# ISOinputs.net
KiCad netlist of a schematic drawn in Altium Designer
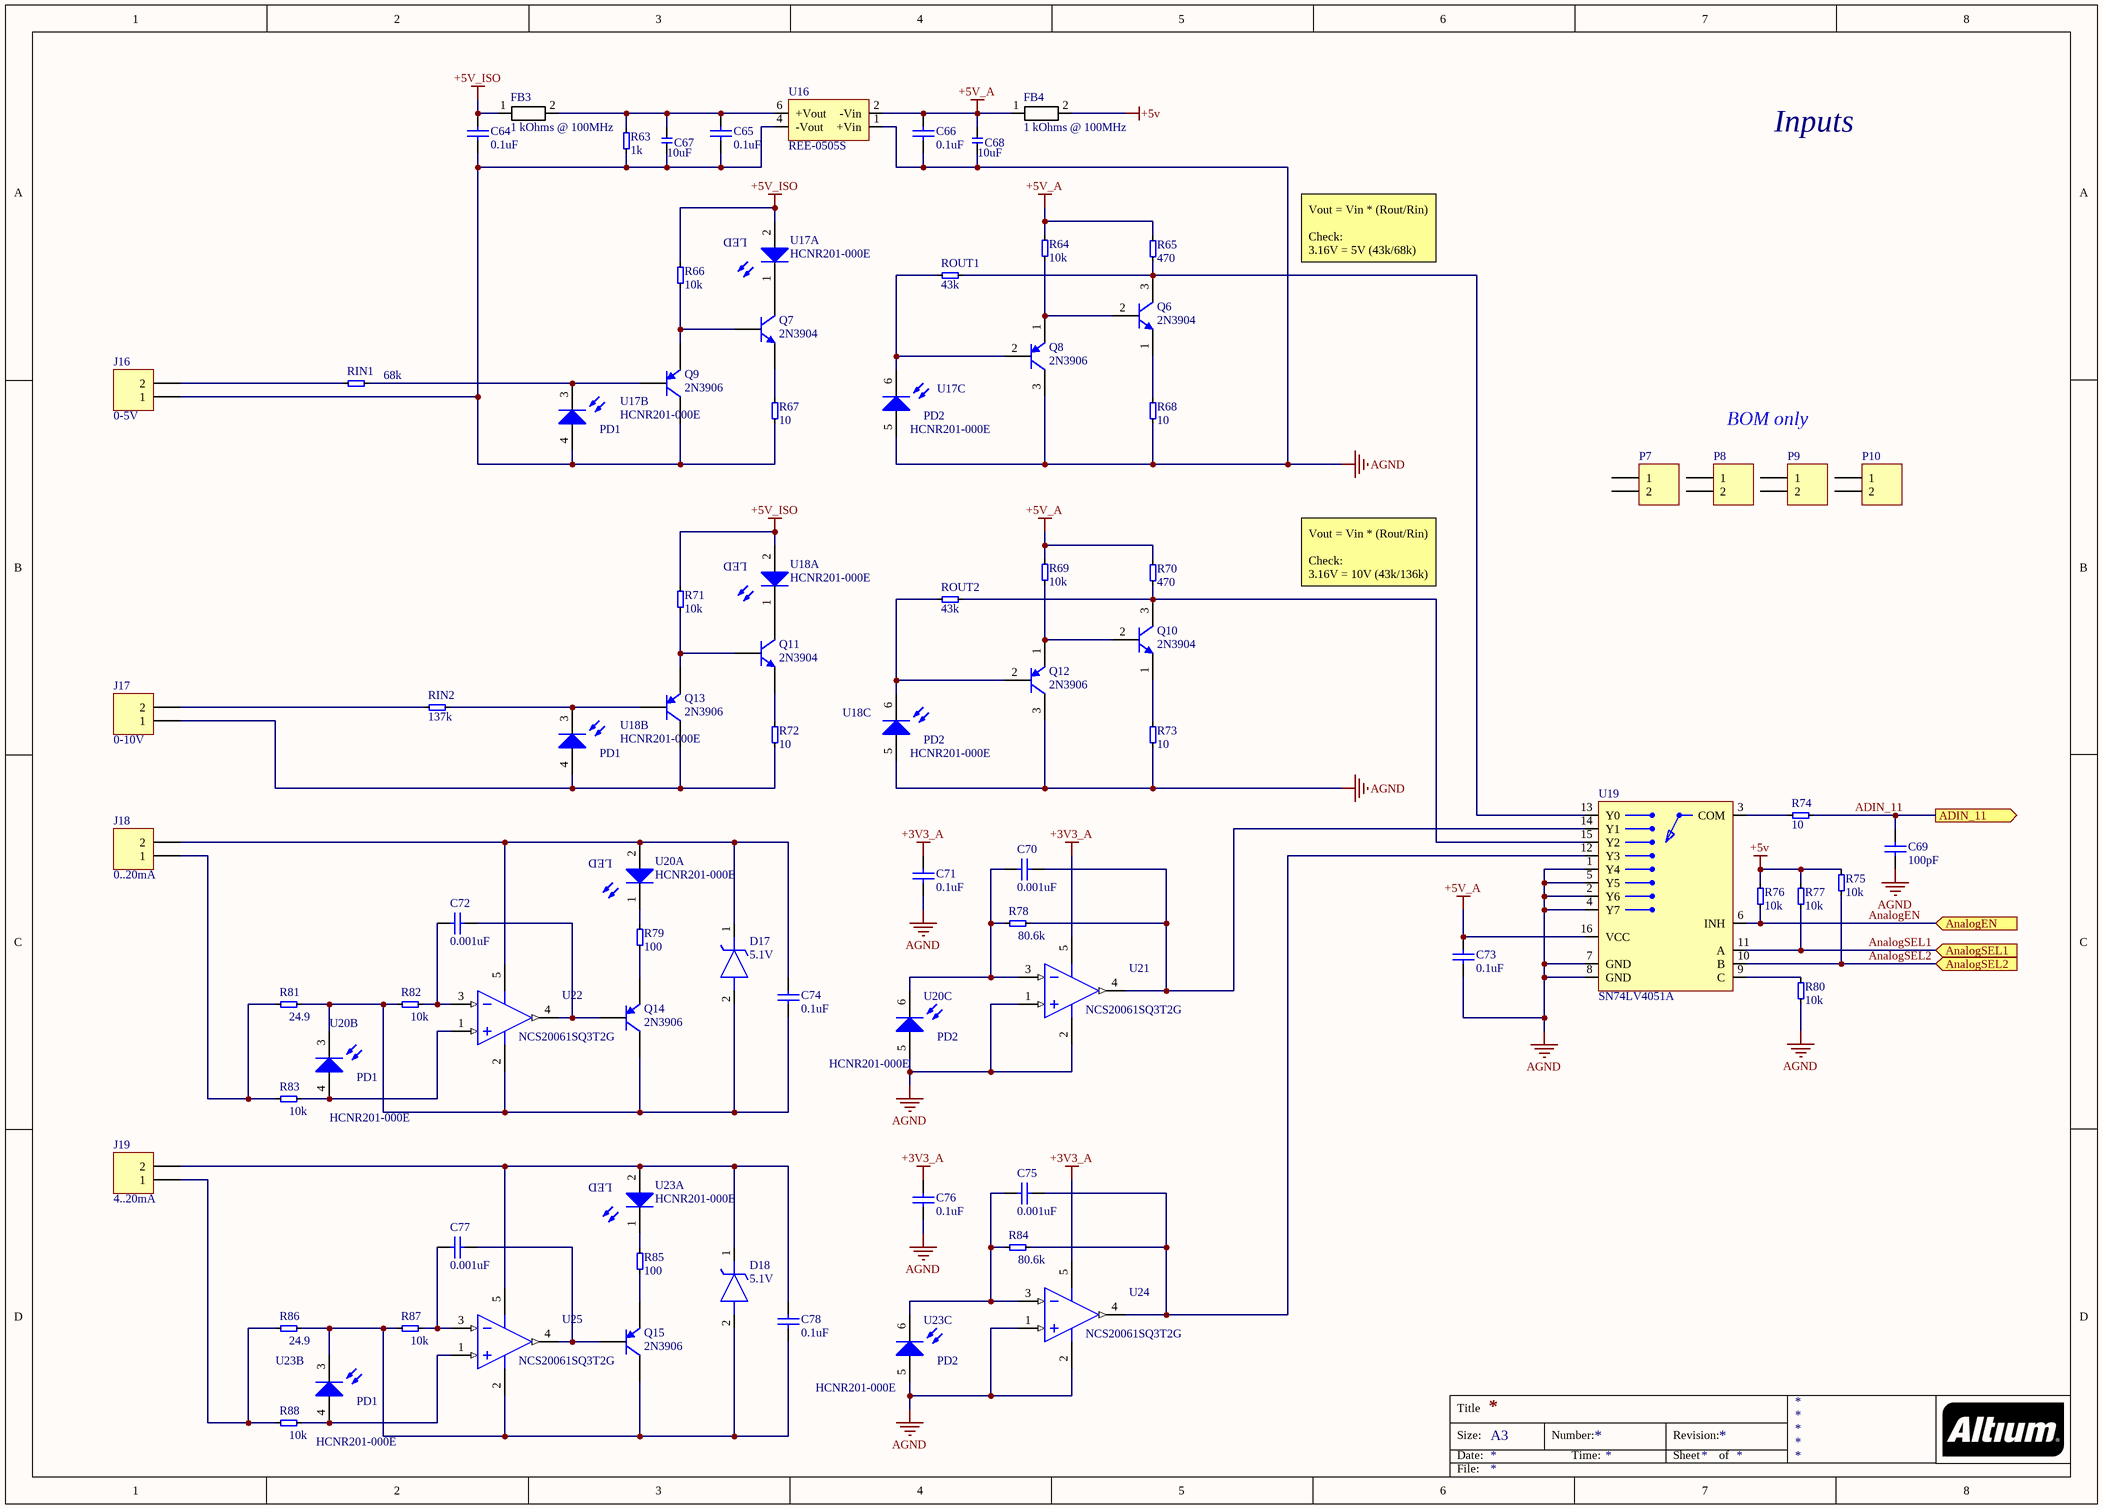
[diagram p0: ISOinputs.SchDoc]

(export (version "E")
  (design (tool "Eeschema 10.0.6"))
  (components
    (comp (ref "C64")
      (value "0.1uF")
      (footprint "C_ceramic_0603")
      (description "CAP CER 0.1UF 50V X7R 0603")
      (fields
        (field (name "MANUFACTURER") "Yageo")
        (field (name "MANUFACTURER PART NUMBER") "CC0603KPX7R9BB104")
      )
      (libsource (lib "Miscellaneous Devices") (part "Cap"))
    )
    (comp (ref "C65")
      (value "0.1uF")
      (footprint "C_ceramic_0603")
      (description "CAP CER 0.1UF 50V X7R 0603")
      (fields
        (field (name "MANUFACTURER") "Yageo")
        (field (name "MANUFACTURER PART NUMBER") "CC0603KPX7R9BB104")
      )
      (libsource (lib "Miscellaneous Devices") (part "Cap"))
    )
    (comp (ref "C66")
      (value "0.1uF")
      (footprint "C_ceramic_0603")
      (description "CAP CER 0.1UF 50V X7R 0603")
      (fields
        (field (name "MANUFACTURER") "Yageo")
        (field (name "MANUFACTURER PART NUMBER") "CC0603KPX7R9BB104")
      )
      (libsource (lib "Miscellaneous Devices") (part "Cap"))
    )
    (comp (ref "C67")
      (value "10uF")
      (footprint "C0603")
      (description "CAP CER 10UF 10V X5R 0603")
      (fields
        (field (name "MANUFACTURER") "Murata")
        (field (name "MANUFACTURER PART NUMBER") "GRM188R61A106KE69D")
      )
      (libsource (lib "LED_LIB") (part "CAP_0603"))
    )
    (comp (ref "C68")
      (value "10uF")
      (footprint "C0603")
      (description "CAP CER 10UF 10V X5R 0603")
      (fields
        (field (name "MANUFACTURER") "Murata")
        (field (name "MANUFACTURER PART NUMBER") "GRM188R61A106KE69D")
      )
      (libsource (lib "LED_LIB") (part "CAP_0603"))
    )
    (comp (ref "C69")
      (value "100pF")
      (footprint "C_ceramic_0603")
      (description "CAP CER 100PF 50V C0G/NPO 0603")
      (fields
        (field (name "MANUFACTURER") "Yageo")
        (field (name "MANUFACTURER PART NUMBER") "CC0603JRNPO9BN101")
      )
      (libsource (lib "Miscellaneous Devices") (part "Cap"))
    )
    (comp (ref "C70")
      (value "0.001uF")
      (footprint "C_ceramic_0603")
      (description "CAP CER 1000PF 50V C0G/NPO 0603")
      (fields
        (field (name "MANUFACTURER") "Yageo")
        (field (name "MANUFACTURER PART NUMBER") "CC0603JRNPO9BN102")
      )
      (libsource (lib "Miscellaneous Devices") (part "Cap"))
    )
    (comp (ref "C71")
      (value "0.1uF")
      (footprint "C_ceramic_0603")
      (description "CAP CER 0.1UF 50V X7R 0603")
      (fields
        (field (name "MANUFACTURER") "Yageo")
        (field (name "MANUFACTURER PART NUMBER") "CC0603KPX7R9BB104")
      )
      (libsource (lib "Miscellaneous Devices") (part "Cap"))
    )
    (comp (ref "C72")
      (value "0.001uF")
      (footprint "C_ceramic_0603")
      (description "CAP CER 1000PF 50V C0G/NPO 0603")
      (fields
        (field (name "MANUFACTURER") "Yageo")
        (field (name "MANUFACTURER PART NUMBER") "CC0603JRNPO9BN102")
      )
      (libsource (lib "Miscellaneous Devices") (part "Cap"))
    )
    (comp (ref "C73")
      (value "0.1uF")
      (footprint "C_ceramic_0603")
      (description "CAP CER 0.1UF 50V X7R 0603")
      (fields
        (field (name "MANUFACTURER") "Yageo")
        (field (name "MANUFACTURER PART NUMBER") "CC0603KPX7R9BB104")
      )
      (libsource (lib "Miscellaneous Devices") (part "Cap"))
    )
    (comp (ref "C74")
      (value "0.1uF")
      (footprint "C_ceramic_0603")
      (description "CAP CER 0.1UF 50V X7R 0603")
      (fields
        (field (name "MANUFACTURER") "Yageo")
        (field (name "MANUFACTURER PART NUMBER") "CC0603KPX7R9BB104")
      )
      (libsource (lib "Miscellaneous Devices") (part "Cap"))
    )
    (comp (ref "C75")
      (value "0.001uF")
      (footprint "C_ceramic_0603")
      (description "CAP CER 1000PF 50V C0G/NPO 0603")
      (fields
        (field (name "MANUFACTURER") "Yageo")
        (field (name "MANUFACTURER PART NUMBER") "CC0603JRNPO9BN102")
      )
      (libsource (lib "Miscellaneous Devices") (part "Cap"))
    )
    (comp (ref "C76")
      (value "0.1uF")
      (footprint "C_ceramic_0603")
      (description "CAP CER 0.1UF 50V X7R 0603")
      (fields
        (field (name "MANUFACTURER") "Yageo")
        (field (name "MANUFACTURER PART NUMBER") "CC0603KPX7R9BB104")
      )
      (libsource (lib "Miscellaneous Devices") (part "Cap"))
    )
    (comp (ref "C77")
      (value "0.001uF")
      (footprint "C_ceramic_0603")
      (description "CAP CER 1000PF 50V C0G/NPO 0603")
      (fields
        (field (name "MANUFACTURER") "Yageo")
        (field (name "MANUFACTURER PART NUMBER") "CC0603JRNPO9BN102")
      )
      (libsource (lib "Miscellaneous Devices") (part "Cap"))
    )
    (comp (ref "C78")
      (value "0.1uF")
      (footprint "C_ceramic_0603")
      (description "CAP CER 0.1UF 50V X7R 0603")
      (fields
        (field (name "MANUFACTURER") "Yageo")
        (field (name "MANUFACTURER PART NUMBER") "CC0603KPX7R9BB104")
      )
      (libsource (lib "Miscellaneous Devices") (part "Cap"))
    )
    (comp (ref "D17")
      (value "5.1V")
      (footprint "SOD_123_CA")
      (description "DIODE ZENER 5.1V 365MW SOD123")
      (fields (field (name "MANUFACTURER") "Nexperia") (field (name "MANUFACTURER PART NUMBER") "PDZ5.1BGWJ"))
      (libsource (lib "MY SCH LIB") (part "ZNR_PLZ5V1C-HG3_H"))
    )
    (comp (ref "D18")
      (value "5.1V")
      (footprint "SOD_123_CA")
      (description "DIODE ZENER 5.1V 365MW SOD123")
      (fields (field (name "MANUFACTURER") "Nexperia") (field (name "MANUFACTURER PART NUMBER") "PDZ5.1BGWJ"))
      (libsource (lib "MY SCH LIB") (part "ZNR_PLZ5V1C-HG3_H"))
    )
    (comp (ref "FB3")
      (value "1 kOhms @ 100MHz")
      (footprint "FB 16080")
      (description "FERRITE BEAD 1 KOHM 0603 1LN")
      (fields
        (field (name "MANUFACTURER") "Wurth Electronics")
        (field (name "MANUFACTURER PART NUMBER") "74279266")
      )
      (libsource (lib "MY SCH LIB") (part "Ferrite bead"))
    )
    (comp (ref "FB4")
      (value "1 kOhms @ 100MHz")
      (footprint "FB 16080")
      (description "FERRITE BEAD 1 KOHM 0603 1LN")
      (fields
        (field (name "MANUFACTURER") "Wurth Electronics")
        (field (name "MANUFACTURER PART NUMBER") "74279266")
      )
      (libsource (lib "MY SCH LIB") (part "Ferrite bead"))
    )
    (comp (ref "J16")
      (value "CIM025P5")
      (footprint "CON2_P5.08_CIM025P5")
      (description "TERM BLK 2P SIDE ENT 5.08MM PCB")
      (fields (field (name "MANUFACTURER") "Sauro"))
      (libsource (lib "") (part "Header 2_1"))
    )
    (comp (ref "J17")
      (value "CIM025P5")
      (footprint "CON2_P5.08_CIM025P5")
      (description "TERM BLK 2P SIDE ENT 5.08MM PCB")
      (fields (field (name "MANUFACTURER") "Sauro"))
      (libsource (lib "") (part "Header 2_1"))
    )
    (comp (ref "J18")
      (value "CIM025P5")
      (footprint "CON2_P5.08_CIM025P5")
      (description "TERM BLK 2P SIDE ENT 5.08MM PCB")
      (fields (field (name "MANUFACTURER") "Sauro"))
      (libsource (lib "") (part "Header 2_1"))
    )
    (comp (ref "J19")
      (value "CIM025P5")
      (footprint "CON2_P5.08_CIM025P5")
      (description "TERM BLK 2P SIDE ENT 5.08MM PCB")
      (fields (field (name "MANUFACTURER") "Sauro"))
      (libsource (lib "") (part "Header 2_1"))
    )
    (comp (ref "P7")
      (value "BOM ONLY")
      (description "Plug")
      (fields (field (name "MANUFACTURER") "Sauro") (field (name "MANUFACTURER PART NUMBER") "CIF02005"))
      (libsource (lib "Miscellaneous Connectors") (part "Header 2"))
    )
    (comp (ref "P8")
      (value "BOM ONLY")
      (description "Plug")
      (fields (field (name "MANUFACTURER") "Sauro") (field (name "MANUFACTURER PART NUMBER") "CIF02005"))
      (libsource (lib "Miscellaneous Connectors") (part "Header 2"))
    )
    (comp (ref "P9")
      (value "BOM ONLY")
      (description "Plug")
      (fields (field (name "MANUFACTURER") "Sauro") (field (name "MANUFACTURER PART NUMBER") "CIF02005"))
      (libsource (lib "Miscellaneous Connectors") (part "Header 2"))
    )
    (comp (ref "P10")
      (value "BOM ONLY")
      (description "Plug")
      (fields (field (name "MANUFACTURER") "Sauro") (field (name "MANUFACTURER PART NUMBER") "CIF02005"))
      (libsource (lib "Miscellaneous Connectors") (part "Header 2"))
    )
    (comp (ref "Q6")
      (value "2N3904")
      (footprint "TO-92A")
      (description "TRANS NPN 40V 0.2A TO-92")
      (fields
        (field (name "MANUFACTURER") "ON Semiconductor / Fairchild")
        (field (name "MANUFACTURER PART NUMBER") "2N3904BU")
      )
      (libsource (lib "") (part "2N3904_1"))
    )
    (comp (ref "Q7")
      (value "2N3904")
      (footprint "TO-92A")
      (description "TRANS NPN 40V 0.2A TO-92")
      (fields
        (field (name "MANUFACTURER") "ON Semiconductor / Fairchild")
        (field (name "MANUFACTURER PART NUMBER") "2N3904BU")
      )
      (libsource (lib "Miscellaneous Devices") (part "2N3904"))
    )
    (comp (ref "Q8")
      (value "2N3906")
      (footprint "TO-92A")
      (description "TRANS PNP 40V TO-92")
      (fields
        (field (name "MANUFACTURER") "Central Semiconductor")
        (field (name "PUBLISHER") "Altium Limited")
      )
      (libsource (lib "Miscellaneous Devices") (part "2N3906"))
    )
    (comp (ref "Q9")
      (value "2N3906")
      (footprint "TO-92A")
      (description "TRANS PNP 40V TO-92")
      (fields
        (field (name "MANUFACTURER") "Central Semiconductor")
        (field (name "PUBLISHER") "Altium Limited")
      )
      (libsource (lib "") (part "2N3906_1"))
    )
    (comp (ref "Q10")
      (value "2N3904")
      (footprint "TO-92A")
      (description "TRANS NPN 40V 0.2A TO-92")
      (fields
        (field (name "MANUFACTURER") "ON Semiconductor / Fairchild")
        (field (name "MANUFACTURER PART NUMBER") "2N3904BU")
      )
      (libsource (lib "") (part "2N3904_1"))
    )
    (comp (ref "Q11")
      (value "2N3904")
      (footprint "TO-92A")
      (description "TRANS NPN 40V 0.2A TO-92")
      (fields
        (field (name "MANUFACTURER") "ON Semiconductor / Fairchild")
        (field (name "MANUFACTURER PART NUMBER") "2N3904BU")
      )
      (libsource (lib "Miscellaneous Devices") (part "2N3904"))
    )
    (comp (ref "Q12")
      (value "2N3906")
      (footprint "TO-92A")
      (description "TRANS PNP 40V TO-92")
      (fields
        (field (name "MANUFACTURER") "Central Semiconductor")
        (field (name "PUBLISHER") "Altium Limited")
      )
      (libsource (lib "Miscellaneous Devices") (part "2N3906"))
    )
    (comp (ref "Q13")
      (value "2N3906")
      (footprint "TO-92A")
      (description "TRANS PNP 40V TO-92")
      (fields
        (field (name "MANUFACTURER") "Central Semiconductor")
        (field (name "PUBLISHER") "Altium Limited")
      )
      (libsource (lib "") (part "2N3906_1"))
    )
    (comp (ref "Q14")
      (value "2N3906")
      (footprint "TO-92A")
      (description "TRANS PNP 40V TO-92")
      (fields (field (name "MANUFACTURER") "Central Semiconductor"))
      (libsource (lib "") (part "2N3906_1"))
    )
    (comp (ref "Q15")
      (value "2N3906")
      (footprint "TO-92A")
      (description "TRANS PNP 40V TO-92")
      (fields (field (name "MANUFACTURER") "Central Semiconductor"))
      (libsource (lib "") (part "2N3906_1"))
    )
    (comp (ref "R63")
      (value "1k")
      (footprint "R_0603")
      (description "RES SMD 1K OHM 1% 1/10W 0603")
      (fields
        (field (name "MANUFACTURER") "Yageo")
        (field (name "MANUFACTURER PART NUMBER") "RC0603FR-071KL")
      )
      (libsource (lib "LED_LIB") (part "R_0402"))
    )
    (comp (ref "R64")
      (value "10k")
      (footprint "R_0603")
      (description "RES SMD 10K OHM 1% 1/10W 0603")
      (fields
        (field (name "MANUFACTURER") "Yageo")
        (field (name "MANUFACTURER PART NUMBER") "RC0603FR-0710KL")
      )
      (libsource (lib "LED_LIB") (part "R_0402"))
    )
    (comp (ref "R65")
      (value "470")
      (footprint "RES_C1206(3216)_M")
      (description "CRGP 1206 470R 1%")
      (fields (field (name "MANUFACTURER") "Yageo") (field (name "MANUFACTURER PART NUMBER") "CRGP1206F470R"))
      (libsource (lib "LED_LIB") (part "R_0402"))
    )
    (comp (ref "R66")
      (value "10k")
      (footprint "R_0603")
      (description "RES SMD 10K OHM 1% 1/10W 0603")
      (fields
        (field (name "MANUFACTURER") "Yageo")
        (field (name "MANUFACTURER PART NUMBER") "RC0603FR-0710KL")
      )
      (libsource (lib "LED_LIB") (part "R_0402"))
    )
    (comp (ref "R67")
      (value "10")
      (footprint "RES_C1206(3216)_M")
      (description "RES SMD 1206 1/2W 1% 10 OHM")
      (fields
        (field (name "MANUFACTURER") "Yageo")
        (field (name "MANUFACTURER PART NUMBER") "SR1206FR-7W10RL")
      )
      (libsource (lib "LED_LIB") (part "R_0402"))
    )
    (comp (ref "R68")
      (value "10")
      (footprint "RES_C1206(3216)_M")
      (description "RES SMD 1206 1/2W 1% 10 OHM")
      (fields
        (field (name "MANUFACTURER") "Yageo")
        (field (name "MANUFACTURER PART NUMBER") "SR1206FR-7W10RL")
      )
      (libsource (lib "LED_LIB") (part "R_0402"))
    )
    (comp (ref "R69")
      (value "10k")
      (footprint "R_0603")
      (description "RES SMD 10K OHM 1% 1/10W 0603")
      (fields
        (field (name "MANUFACTURER") "Yageo")
        (field (name "MANUFACTURER PART NUMBER") "RC0603FR-0710KL")
      )
      (libsource (lib "LED_LIB") (part "R_0402"))
    )
    (comp (ref "R70")
      (value "470")
      (footprint "RES_C1206(3216)_M")
      (description "CRGP 1206 470R 1%")
      (fields (field (name "MANUFACTURER") "Yageo") (field (name "MANUFACTURER PART NUMBER") "CRGP1206F470R"))
      (libsource (lib "LED_LIB") (part "R_0402"))
    )
    (comp (ref "R71")
      (value "10k")
      (footprint "R_0603")
      (description "RES SMD 10K OHM 1% 1/10W 0603")
      (fields
        (field (name "MANUFACTURER") "Yageo")
        (field (name "MANUFACTURER PART NUMBER") "RC0603FR-0710KL")
      )
      (libsource (lib "LED_LIB") (part "R_0402"))
    )
    (comp (ref "R72")
      (value "10")
      (footprint "RES_C1206(3216)_M")
      (description "RES SMD 1206 1/2W 1% 10 OHM")
      (fields
        (field (name "MANUFACTURER") "Yageo")
        (field (name "MANUFACTURER PART NUMBER") "SR1206FR-7W10RL")
      )
      (libsource (lib "LED_LIB") (part "R_0402"))
    )
    (comp (ref "R73")
      (value "10")
      (footprint "RES_C1206(3216)_M")
      (description "RES SMD 1206 1/2W 1% 10 OHM")
      (fields
        (field (name "MANUFACTURER") "Yageo")
        (field (name "MANUFACTURER PART NUMBER") "SR1206FR-7W10RL")
      )
      (libsource (lib "LED_LIB") (part "R_0402"))
    )
    (comp (ref "R74")
      (value "10")
      (footprint "R_0603")
      (description "RES SMD 10 OHM 1% 1/10W 0603")
      (fields
        (field (name "MANUFACTURER") "Yageo")
        (field (name "MANUFACTURER PART NUMBER") "RC0603FR-0710RL")
      )
      (libsource (lib "LED_LIB") (part "R_0402"))
    )
    (comp (ref "R75")
      (value "10k")
      (footprint "R_0603")
      (description "RES SMD 10K OHM 1% 1/10W 0603")
      (fields
        (field (name "MANUFACTURER") "Yageo")
        (field (name "MANUFACTURER PART NUMBER") "RC0603FR-0710KL")
      )
      (libsource (lib "LED_LIB") (part "R_0402"))
    )
    (comp (ref "R76")
      (value "10k")
      (footprint "R_0603")
      (description "RES SMD 10K OHM 1% 1/10W 0603")
      (fields
        (field (name "MANUFACTURER") "Yageo")
        (field (name "MANUFACTURER PART NUMBER") "RC0603FR-0710KL")
      )
      (libsource (lib "LED_LIB") (part "R_0402"))
    )
    (comp (ref "R77")
      (value "10k")
      (footprint "R_0603")
      (description "RES SMD 10K OHM 1% 1/10W 0603")
      (fields
        (field (name "MANUFACTURER") "Yageo")
        (field (name "MANUFACTURER PART NUMBER") "RC0603FR-0710KL")
      )
      (libsource (lib "LED_LIB") (part "R_0402"))
    )
    (comp (ref "R78")
      (value "80.6k")
      (footprint "R_0603")
      (description "RES SMD 80.6K OHM 1% 1/10W 0603")
      (fields
        (field (name "MANUFACTURER") "Yageo")
        (field (name "MANUFACTURER PART NUMBER") "RC0603FR-0780K6L")
      )
      (libsource (lib "LED_LIB") (part "R_0402"))
    )
    (comp (ref "R79")
      (value "100")
      (footprint "R_0603")
      (description "RES SMD 100 OHM 1% 1/10W 0603")
      (fields
        (field (name "MANUFACTURER") "Yageo")
        (field (name "MANUFACTURER PART NUMBER") "RC0603FR-07100RL")
      )
      (libsource (lib "LED_LIB") (part "R_0402"))
    )
    (comp (ref "R80")
      (value "10k")
      (footprint "R_0603")
      (description "RES SMD 10K OHM 1% 1/10W 0603")
      (fields
        (field (name "MANUFACTURER") "Yageo")
        (field (name "MANUFACTURER PART NUMBER") "RC0603FR-0710KL")
      )
      (libsource (lib "LED_LIB") (part "R_0402"))
    )
    (comp (ref "R81")
      (value "24.9")
      (footprint "R_0603")
      (description "RES SMD 24.9 OHM 1% 1/10W 0603")
      (fields
        (field (name "MANUFACTURER") "Yageo")
        (field (name "MANUFACTURER PART NUMBER") "RC0603FR-0724R9L")
      )
      (libsource (lib "LED_LIB") (part "R_0402"))
    )
    (comp (ref "R82")
      (value "10k")
      (footprint "R_0603")
      (description "RES SMD 10K OHM 1% 1/10W 0603")
      (fields
        (field (name "MANUFACTURER") "Yageo")
        (field (name "MANUFACTURER PART NUMBER") "RC0603FR-0710KL")
      )
      (libsource (lib "LED_LIB") (part "R_0402"))
    )
    (comp (ref "R83")
      (value "10k")
      (footprint "R_0603")
      (description "RES SMD 10K OHM 1% 1/10W 0603")
      (fields
        (field (name "MANUFACTURER") "Yageo")
        (field (name "MANUFACTURER PART NUMBER") "RC0603FR-0710KL")
      )
      (libsource (lib "LED_LIB") (part "R_0402"))
    )
    (comp (ref "R84")
      (value "80.6k")
      (footprint "R_0603")
      (description "RES SMD 80.6K OHM 1% 1/10W 0603")
      (fields
        (field (name "MANUFACTURER") "Yageo")
        (field (name "MANUFACTURER PART NUMBER") "RC0603FR-0780K6L")
      )
      (libsource (lib "LED_LIB") (part "R_0402"))
    )
    (comp (ref "R85")
      (value "100")
      (footprint "R_0603")
      (description "RES SMD 100 OHM 1% 1/10W 0603")
      (fields
        (field (name "MANUFACTURER") "Yageo")
        (field (name "MANUFACTURER PART NUMBER") "RC0603FR-07100RL")
      )
      (libsource (lib "LED_LIB") (part "R_0402"))
    )
    (comp (ref "R86")
      (value "24.9")
      (footprint "R_0603")
      (description "RES SMD 24.9 OHM 1% 1/10W 0603")
      (fields
        (field (name "MANUFACTURER") "Yageo")
        (field (name "MANUFACTURER PART NUMBER") "RC0603FR-0724R9L")
      )
      (libsource (lib "LED_LIB") (part "R_0402"))
    )
    (comp (ref "R87")
      (value "10k")
      (footprint "R_0603")
      (description "RES SMD 10K OHM 1% 1/10W 0603")
      (fields
        (field (name "MANUFACTURER") "Yageo")
        (field (name "MANUFACTURER PART NUMBER") "RC0603FR-0710KL")
      )
      (libsource (lib "LED_LIB") (part "R_0402"))
    )
    (comp (ref "R88")
      (value "10k")
      (footprint "R_0603")
      (description "RES SMD 10K OHM 1% 1/10W 0603")
      (fields
        (field (name "MANUFACTURER") "Yageo")
        (field (name "MANUFACTURER PART NUMBER") "RC0603FR-0710KL")
      )
      (libsource (lib "LED_LIB") (part "R_0402"))
    )
    (comp (ref "RIN1")
      (value "68k")
      (footprint "R_0603")
      (description "RES SMD 1206 1/2W 1% 10 OHM")
      (fields
        (field (name "MANUFACTURER") "Yageo")
        (field (name "MANUFACTURER PART NUMBER") "SR1206FR-7W10RL")
      )
      (libsource (lib "LED_LIB") (part "R_0402"))
    )
    (comp (ref "RIN2")
      (value "137k")
      (footprint "R_0603")
      (description "RES SMD 1206 1/2W 1% 10 OHM")
      (fields
        (field (name "MANUFACTURER") "Yageo")
        (field (name "MANUFACTURER PART NUMBER") "SR1206FR-7W10RL")
      )
      (libsource (lib "LED_LIB") (part "R_0402"))
    )
    (comp (ref "ROUT1")
      (value "43k")
      (footprint "R_0603")
      (description "RES SMD 43K OHM 1% 1/10W 0603")
      (fields
        (field (name "MANUFACTURER") "Yageo")
        (field (name "MANUFACTURER PART NUMBER") "RC0603FR-0743KL")
      )
      (libsource (lib "LED_LIB") (part "R_0402"))
    )
    (comp (ref "ROUT2")
      (value "43k")
      (footprint "R_0603")
      (description "RES SMD 43K OHM 1% 1/10W 0603")
      (fields
        (field (name "MANUFACTURER") "Yageo")
        (field (name "MANUFACTURER PART NUMBER") "RC0603FR-0743KL")
      )
      (libsource (lib "LED_LIB") (part "R_0402"))
    )
    (comp (ref "U16")
      (value "REE-0505S")
      (footprint "SIP_7")
      (description "DC DC CONVERTER 5V 1W")
      (fields (field (name "MANUFACTURER") "Recom"))
      (libsource (lib "SHEYKO") (part "IK0505SA"))
    )
    (comp (ref "U17")
      (value "HCNR201-000E")
      (footprint "dip_8")
      (description "OPTOISO 5KV LINEAR PHVOLT 8DIP")
      (fields (field (name "MANUFACTURER") "Broadcom"))
      (libsource (lib "SHEYKO") (part "HCNR200"))
    )
    (comp (ref "U18")
      (value "HCNR201-000E")
      (footprint "dip_8")
      (description "OPTOISO 5KV LINEAR PHVOLT 8DIP")
      (fields (field (name "MANUFACTURER") "Broadcom"))
      (libsource (lib "SHEYKO") (part "HCNR200"))
    )
    (comp (ref "U19")
      (value "SN74LV4051A")
      (footprint "SOIC-16_10x4mm_P1.27")
      (description "IC MUX/DEMUX 8X1 16SOIC")
      (fields
        (field (name "MANUFACTURER") "Texas Instruments")
        (field (name "MANUFACTURER PART NUMBER") "SN74LV4051ADR")
      )
      (libsource (lib "SHEYKO") (part "SN74LV4051A"))
    )
    (comp (ref "U20")
      (value "HCNR201-000E")
      (footprint "dip_8")
      (description "OPTOISO 5KV LINEAR PHVOLT 8DIP")
      (fields (field (name "MANUFACTURER") "Broadcom"))
      (libsource (lib "SHEYKO") (part "HCNR200"))
    )
    (comp (ref "U21")
      (value "NCS20061SQ3T2G")
      (footprint "SOT-353-5")
      (description "IC OPAMP GP 1 CIRCUIT SC88A")
      (fields (field (name "MANUFACTURER") "ON Semiconductor"))
      (libsource (lib "SHEYKO") (part "AMP OP"))
    )
    (comp (ref "U22")
      (value "NCS20061SQ3T2G")
      (footprint "SOT-353-5")
      (description "IC OPAMP GP 1 CIRCUIT SC88A")
      (fields (field (name "MANUFACTURER") "ON Semiconductor"))
      (libsource (lib "SHEYKO") (part "AMP OP"))
    )
    (comp (ref "U23")
      (value "HCNR201-000E")
      (footprint "dip_8")
      (description "OPTOISO 5KV LINEAR PHVOLT 8DIP")
      (fields (field (name "MANUFACTURER") "Broadcom"))
      (libsource (lib "SHEYKO") (part "HCNR200"))
    )
    (comp (ref "U24")
      (value "NCS20061SQ3T2G")
      (footprint "SOT-353-5")
      (description "IC OPAMP GP 1 CIRCUIT SC88A")
      (fields (field (name "MANUFACTURER") "ON Semiconductor"))
      (libsource (lib "SHEYKO") (part "AMP OP"))
    )
    (comp (ref "U25")
      (value "NCS20061SQ3T2G")
      (footprint "SOT-353-5")
      (description "IC OPAMP GP 1 CIRCUIT SC88A")
      (fields (field (name "MANUFACTURER") "ON Semiconductor"))
      (libsource (lib "SHEYKO") (part "AMP OP"))
    )
  )
  (nets
    (net (code "1") (name "+3V3_A") (class "Default")
      (node (ref "C71") (pin "2") (pinfunction "2_2") (pintype "passive"))
      (node (ref "C76") (pin "2") (pinfunction "2_2") (pintype "passive"))
      (node (ref "U21") (pin "5") (pinfunction "V+_5") (pintype "power_in"))
      (node (ref "U24") (pin "5") (pinfunction "V+_5") (pintype "power_in"))
    )
    (net (code "2") (name "+5V_A") (class "Default")
      (node (ref "C66") (pin "2") (pinfunction "2_2") (pintype "passive"))
      (node (ref "C68") (pin "2") (pinfunction "2_2") (pintype "passive"))
      (node (ref "C73") (pin "2") (pinfunction "2_2") (pintype "passive"))
      (node (ref "FB4") (pin "1") (pintype "passive"))
      (node (ref "R64") (pin "1") (pinfunction "1_1") (pintype "passive"))
      (node (ref "R65") (pin "1") (pinfunction "1_1") (pintype "passive"))
      (node (ref "R69") (pin "1") (pinfunction "1_1") (pintype "passive"))
      (node (ref "R70") (pin "1") (pinfunction "1_1") (pintype "passive"))
      (node (ref "U16") (pin "2") (pinfunction "-Vin_2") (pintype "passive"))
      (node (ref "U19") (pin "16") (pinfunction "VCC_16") (pintype "passive"))
    )
    (net (code "3") (name "+5V_ISO") (class "Default")
      (node (ref "C64") (pin "2") (pinfunction "2_2") (pintype "passive"))
      (node (ref "FB3") (pin "1") (pintype "passive"))
      (node (ref "R66") (pin "1") (pinfunction "1_1") (pintype "passive"))
      (node (ref "R71") (pin "1") (pinfunction "1_1") (pintype "passive"))
      (node (ref "U17") (pin "2") (pinfunction "A_2") (pintype "passive"))
      (node (ref "U18") (pin "2") (pinfunction "A_2") (pintype "passive"))
    )
    (net (code "4") (name "+5v") (class "Default")
      (node (ref "FB4") (pin "2") (pintype "passive"))
      (node (ref "R75") (pin "2") (pinfunction "2_2") (pintype "passive"))
      (node (ref "R76") (pin "2") (pinfunction "2_2") (pintype "passive"))
      (node (ref "R77") (pin "2") (pinfunction "2_2") (pintype "passive"))
    )
    (net (code "5") (name "/ADIN_11") (class "Default")
      (node (ref "C69") (pin "2") (pinfunction "2_2") (pintype "passive"))
      (node (ref "R74") (pin "2") (pinfunction "2_2") (pintype "passive"))
    )
    (net (code "6") (name "/AnalogEN") (class "Default")
      (node (ref "R76") (pin "1") (pinfunction "1_1") (pintype "passive"))
      (node (ref "U19") (pin "6") (pinfunction "INH_6") (pintype "passive"))
    )
    (net (code "7") (name "/AnalogSEL1") (class "Default")
      (node (ref "R77") (pin "1") (pinfunction "1_1") (pintype "passive"))
      (node (ref "U19") (pin "11") (pinfunction "A_11") (pintype "passive"))
    )
    (net (code "8") (name "/AnalogSEL2") (class "Default")
      (node (ref "R75") (pin "1") (pinfunction "1_1") (pintype "passive"))
      (node (ref "U19") (pin "10") (pinfunction "B_10") (pintype "passive"))
    )
    (net (code "9") (name "AGND") (class "Default")
      (node (ref "C66") (pin "1") (pinfunction "1_1") (pintype "passive"))
      (node (ref "C68") (pin "1") (pinfunction "1_1") (pintype "passive"))
      (node (ref "C69") (pin "1") (pinfunction "1_1") (pintype "passive"))
      (node (ref "C71") (pin "1") (pinfunction "1_1") (pintype "passive"))
      (node (ref "C73") (pin "1") (pinfunction "1_1") (pintype "passive"))
      (node (ref "C76") (pin "1") (pinfunction "1_1") (pintype "passive"))
      (node (ref "Q12") (pin "3") (pinfunction "C_3") (pintype "passive"))
      (node (ref "Q8") (pin "3") (pinfunction "C_3") (pintype "passive"))
      (node (ref "R68") (pin "2") (pinfunction "2_2") (pintype "passive"))
      (node (ref "R73") (pin "2") (pinfunction "2_2") (pintype "passive"))
      (node (ref "R80") (pin "1") (pinfunction "1_1") (pintype "passive"))
      (node (ref "U16") (pin "1") (pinfunction "+Vin_1") (pintype "passive"))
      (node (ref "U17") (pin "5") (pinfunction "A_5") (pintype "passive"))
      (node (ref "U18") (pin "5") (pinfunction "A_5") (pintype "passive"))
      (node (ref "U19") (pin "1") (pinfunction "Y4_1") (pintype "passive"))
      (node (ref "U19") (pin "2") (pinfunction "Y6_2") (pintype "passive"))
      (node (ref "U19") (pin "4") (pinfunction "Y7_4") (pintype "passive"))
      (node (ref "U19") (pin "5") (pinfunction "Y5_5") (pintype "passive"))
      (node (ref "U19") (pin "7") (pinfunction "GND_7") (pintype "passive"))
      (node (ref "U19") (pin "8") (pinfunction "GND_8") (pintype "passive"))
      (node (ref "U20") (pin "5") (pinfunction "A_5") (pintype "passive"))
      (node (ref "U21") (pin "1") (pinfunction "+IN_1") (pintype "input"))
      (node (ref "U21") (pin "2") (pinfunction "V-_2") (pintype "power_in"))
      (node (ref "U23") (pin "5") (pinfunction "A_5") (pintype "passive"))
      (node (ref "U24") (pin "1") (pinfunction "+IN_1") (pintype "input"))
      (node (ref "U24") (pin "2") (pinfunction "V-_2") (pintype "power_in"))
    )
    (net (code "10") (name "Net-(D17-A)") (class "Default")
      (node (ref "C74") (pin "2") (pinfunction "2_2") (pintype "passive"))
      (node (ref "D17") (pin "2") (pinfunction "A_2") (pintype "passive"))
      (node (ref "Q14") (pin "3") (pinfunction "C_3") (pintype "passive"))
      (node (ref "R81") (pin "1") (pinfunction "1_1") (pintype "passive"))
      (node (ref "R82") (pin "2") (pinfunction "2_2") (pintype "passive"))
      (node (ref "U20") (pin "3") (pinfunction "K_3") (pintype "passive"))
      (node (ref "U22") (pin "2") (pinfunction "V-_2") (pintype "power_in"))
    )
    (net (code "11") (name "Net-(D17-K)") (class "Default")
      (node (ref "C74") (pin "1") (pinfunction "1_1") (pintype "passive"))
      (node (ref "D17") (pin "1") (pinfunction "K_1") (pintype "passive"))
      (node (ref "J18") (pin "2") (pinfunction "2_2") (pintype "passive"))
      (node (ref "U20") (pin "2") (pinfunction "A_2") (pintype "passive"))
      (node (ref "U22") (pin "5") (pinfunction "V+_5") (pintype "power_in"))
    )
    (net (code "12") (name "Net-(D18-A)") (class "Default")
      (node (ref "C78") (pin "2") (pinfunction "2_2") (pintype "passive"))
      (node (ref "D18") (pin "2") (pinfunction "A_2") (pintype "passive"))
      (node (ref "Q15") (pin "3") (pinfunction "C_3") (pintype "passive"))
      (node (ref "R86") (pin "1") (pinfunction "1_1") (pintype "passive"))
      (node (ref "R87") (pin "2") (pinfunction "2_2") (pintype "passive"))
      (node (ref "U23") (pin "3") (pinfunction "K_3") (pintype "passive"))
      (node (ref "U25") (pin "2") (pinfunction "V-_2") (pintype "power_in"))
    )
    (net (code "13") (name "Net-(D18-K)") (class "Default")
      (node (ref "C78") (pin "1") (pinfunction "1_1") (pintype "passive"))
      (node (ref "D18") (pin "1") (pinfunction "K_1") (pintype "passive"))
      (node (ref "J19") (pin "2") (pinfunction "2_2") (pintype "passive"))
      (node (ref "U23") (pin "2") (pinfunction "A_2") (pintype "passive"))
      (node (ref "U25") (pin "5") (pinfunction "V+_5") (pintype "power_in"))
    )
    (net (code "14") (name "Net-(J16-Pad2)") (class "Default")
      (node (ref "J16") (pin "2") (pinfunction "2_2") (pintype "passive"))
      (node (ref "RIN1") (pin "1") (pinfunction "1_1") (pintype "passive"))
    )
    (net (code "15") (name "Net-(J17-Pad2)") (class "Default")
      (node (ref "J17") (pin "2") (pinfunction "2_2") (pintype "passive"))
      (node (ref "RIN2") (pin "1") (pinfunction "1_1") (pintype "passive"))
    )
    (net (code "16") (name "Net-(J18-Pad1)") (class "Default")
      (node (ref "J18") (pin "1") (pinfunction "1_1") (pintype "passive"))
      (node (ref "R81") (pin "2") (pinfunction "2_2") (pintype "passive"))
      (node (ref "R83") (pin "2") (pinfunction "2_2") (pintype "passive"))
    )
    (net (code "17") (name "Net-(J19-Pad1)") (class "Default")
      (node (ref "J19") (pin "1") (pinfunction "1_1") (pintype "passive"))
      (node (ref "R86") (pin "2") (pinfunction "2_2") (pintype "passive"))
      (node (ref "R88") (pin "2") (pinfunction "2_2") (pintype "passive"))
    )
    (net (code "18") (name "Net-(Q6-B)") (class "Default")
      (node (ref "Q6") (pin "2") (pinfunction "B_2") (pintype "passive"))
      (node (ref "Q8") (pin "1") (pinfunction "E_1") (pintype "passive"))
      (node (ref "R64") (pin "2") (pinfunction "2_2") (pintype "passive"))
    )
    (net (code "19") (name "Net-(Q6-C)") (class "Default")
      (node (ref "Q6") (pin "3") (pinfunction "C_3") (pintype "passive"))
      (node (ref "R65") (pin "2") (pinfunction "2_2") (pintype "passive"))
      (node (ref "ROUT1") (pin "2") (pinfunction "2_2") (pintype "passive"))
      (node (ref "U19") (pin "13") (pinfunction "Y0_13") (pintype "passive"))
    )
    (net (code "20") (name "Net-(Q6-E)") (class "Default")
      (node (ref "Q6") (pin "1") (pinfunction "E_1") (pintype "passive"))
      (node (ref "R68") (pin "1") (pinfunction "1_1") (pintype "passive"))
    )
    (net (code "21") (name "Net-(Q7-B)") (class "Default")
      (node (ref "Q7") (pin "2") (pinfunction "B_2") (pintype "passive"))
      (node (ref "Q9") (pin "1") (pinfunction "E_1") (pintype "passive"))
      (node (ref "R66") (pin "2") (pinfunction "2_2") (pintype "passive"))
    )
    (net (code "22") (name "Net-(Q7-C)") (class "Default")
      (node (ref "Q7") (pin "3") (pinfunction "C_3") (pintype "passive"))
      (node (ref "U17") (pin "1") (pinfunction "K_1") (pintype "passive"))
    )
    (net (code "23") (name "Net-(Q7-E)") (class "Default")
      (node (ref "Q7") (pin "1") (pinfunction "E_1") (pintype "passive"))
      (node (ref "R67") (pin "1") (pinfunction "1_1") (pintype "passive"))
    )
    (net (code "24") (name "Net-(Q8-B)") (class "Default")
      (node (ref "Q8") (pin "2") (pinfunction "B_2") (pintype "passive"))
      (node (ref "ROUT1") (pin "1") (pinfunction "1_1") (pintype "passive"))
      (node (ref "U17") (pin "6") (pinfunction "K_6") (pintype "passive"))
    )
    (net (code "25") (name "Net-(Q9-B)") (class "Default")
      (node (ref "Q9") (pin "2") (pinfunction "B_2") (pintype "passive"))
      (node (ref "RIN1") (pin "2") (pinfunction "2_2") (pintype "passive"))
      (node (ref "U17") (pin "3") (pinfunction "K_3") (pintype "passive"))
    )
    (net (code "26") (name "Net-(Q9-C)") (class "Default")
      (node (ref "C64") (pin "1") (pinfunction "1_1") (pintype "passive"))
      (node (ref "C65") (pin "1") (pinfunction "1_1") (pintype "passive"))
      (node (ref "C67") (pin "1") (pinfunction "1_1") (pintype "passive"))
      (node (ref "J16") (pin "1") (pinfunction "1_1") (pintype "passive"))
      (node (ref "Q9") (pin "3") (pinfunction "C_3") (pintype "passive"))
      (node (ref "R63") (pin "2") (pinfunction "2_2") (pintype "passive"))
      (node (ref "R67") (pin "2") (pinfunction "2_2") (pintype "passive"))
      (node (ref "U16") (pin "4") (pinfunction "-Vout_4") (pintype "passive"))
      (node (ref "U17") (pin "4") (pinfunction "A_4") (pintype "passive"))
    )
    (net (code "27") (name "Net-(Q10-B)") (class "Default")
      (node (ref "Q10") (pin "2") (pinfunction "B_2") (pintype "passive"))
      (node (ref "Q12") (pin "1") (pinfunction "E_1") (pintype "passive"))
      (node (ref "R69") (pin "2") (pinfunction "2_2") (pintype "passive"))
    )
    (net (code "28") (name "Net-(Q10-C)") (class "Default")
      (node (ref "Q10") (pin "3") (pinfunction "C_3") (pintype "passive"))
      (node (ref "R70") (pin "2") (pinfunction "2_2") (pintype "passive"))
      (node (ref "ROUT2") (pin "2") (pinfunction "2_2") (pintype "passive"))
      (node (ref "U19") (pin "15") (pinfunction "Y2_15") (pintype "passive"))
    )
    (net (code "29") (name "Net-(Q10-E)") (class "Default")
      (node (ref "Q10") (pin "1") (pinfunction "E_1") (pintype "passive"))
      (node (ref "R73") (pin "1") (pinfunction "1_1") (pintype "passive"))
    )
    (net (code "30") (name "Net-(Q11-B)") (class "Default")
      (node (ref "Q11") (pin "2") (pinfunction "B_2") (pintype "passive"))
      (node (ref "Q13") (pin "1") (pinfunction "E_1") (pintype "passive"))
      (node (ref "R71") (pin "2") (pinfunction "2_2") (pintype "passive"))
    )
    (net (code "31") (name "Net-(Q11-C)") (class "Default")
      (node (ref "Q11") (pin "3") (pinfunction "C_3") (pintype "passive"))
      (node (ref "U18") (pin "1") (pinfunction "K_1") (pintype "passive"))
    )
    (net (code "32") (name "Net-(Q11-E)") (class "Default")
      (node (ref "Q11") (pin "1") (pinfunction "E_1") (pintype "passive"))
      (node (ref "R72") (pin "1") (pinfunction "1_1") (pintype "passive"))
    )
    (net (code "33") (name "Net-(Q12-B)") (class "Default")
      (node (ref "Q12") (pin "2") (pinfunction "B_2") (pintype "passive"))
      (node (ref "ROUT2") (pin "1") (pinfunction "1_1") (pintype "passive"))
      (node (ref "U18") (pin "6") (pinfunction "K_6") (pintype "passive"))
    )
    (net (code "34") (name "Net-(Q13-B)") (class "Default")
      (node (ref "Q13") (pin "2") (pinfunction "B_2") (pintype "passive"))
      (node (ref "RIN2") (pin "2") (pinfunction "2_2") (pintype "passive"))
      (node (ref "U18") (pin "3") (pinfunction "K_3") (pintype "passive"))
    )
    (net (code "35") (name "Net-(Q13-C)") (class "Default")
      (node (ref "J17") (pin "1") (pinfunction "1_1") (pintype "passive"))
      (node (ref "Q13") (pin "3") (pinfunction "C_3") (pintype "passive"))
      (node (ref "R72") (pin "2") (pinfunction "2_2") (pintype "passive"))
      (node (ref "U18") (pin "4") (pinfunction "A_4") (pintype "passive"))
    )
    (net (code "36") (name "Net-(Q14-B)") (class "Default")
      (node (ref "C72") (pin "2") (pinfunction "2_2") (pintype "passive"))
      (node (ref "Q14") (pin "2") (pinfunction "B_2") (pintype "passive"))
      (node (ref "U22") (pin "4") (pinfunction "OUT_4") (pintype "output"))
    )
    (net (code "37") (name "Net-(Q14-E)") (class "Default")
      (node (ref "Q14") (pin "1") (pinfunction "E_1") (pintype "passive"))
      (node (ref "R79") (pin "2") (pinfunction "2_2") (pintype "passive"))
    )
    (net (code "38") (name "Net-(Q15-B)") (class "Default")
      (node (ref "C77") (pin "2") (pinfunction "2_2") (pintype "passive"))
      (node (ref "Q15") (pin "2") (pinfunction "B_2") (pintype "passive"))
      (node (ref "U25") (pin "4") (pinfunction "OUT_4") (pintype "output"))
    )
    (net (code "39") (name "Net-(Q15-E)") (class "Default")
      (node (ref "Q15") (pin "1") (pinfunction "E_1") (pintype "passive"))
      (node (ref "R85") (pin "2") (pinfunction "2_2") (pintype "passive"))
    )
    (net (code "40") (name "Net-(U16-+Vout)") (class "Default")
      (node (ref "C65") (pin "2") (pinfunction "2_2") (pintype "passive"))
      (node (ref "C67") (pin "2") (pinfunction "2_2") (pintype "passive"))
      (node (ref "FB3") (pin "2") (pintype "passive"))
      (node (ref "R63") (pin "1") (pinfunction "1_1") (pintype "passive"))
      (node (ref "U16") (pin "6") (pinfunction "+Vout_6") (pintype "passive"))
    )
    (net (code "41") (name "Net-(U19-C)") (class "Default")
      (node (ref "R80") (pin "2") (pinfunction "2_2") (pintype "passive"))
      (node (ref "U19") (pin "9") (pinfunction "C_9") (pintype "passive"))
    )
    (net (code "42") (name "Net-(U19-COM)") (class "Default")
      (node (ref "R74") (pin "1") (pinfunction "1_1") (pintype "passive"))
      (node (ref "U19") (pin "3") (pinfunction "COM_3") (pintype "passive"))
    )
    (net (code "43") (name "Net-(U19-Y1)") (class "Default")
      (node (ref "C70") (pin "2") (pinfunction "2_2") (pintype "passive"))
      (node (ref "R78") (pin "1") (pinfunction "1_1") (pintype "passive"))
      (node (ref "U19") (pin "14") (pinfunction "Y1_14") (pintype "passive"))
      (node (ref "U21") (pin "4") (pinfunction "OUT_4") (pintype "output"))
    )
    (net (code "44") (name "Net-(U19-Y3)") (class "Default")
      (node (ref "C75") (pin "2") (pinfunction "2_2") (pintype "passive"))
      (node (ref "R84") (pin "1") (pinfunction "1_1") (pintype "passive"))
      (node (ref "U19") (pin "12") (pinfunction "Y3_12") (pintype "passive"))
      (node (ref "U24") (pin "4") (pinfunction "OUT_4") (pintype "output"))
    )
    (net (code "45") (name "Net-(U20A-K)") (class "Default")
      (node (ref "R79") (pin "1") (pinfunction "1_1") (pintype "passive"))
      (node (ref "U20") (pin "1") (pinfunction "K_1") (pintype "passive"))
    )
    (net (code "46") (name "Net-(U20B-A)") (class "Default")
      (node (ref "R83") (pin "1") (pinfunction "1_1") (pintype "passive"))
      (node (ref "U20") (pin "4") (pinfunction "A_4") (pintype "passive"))
      (node (ref "U22") (pin "1") (pinfunction "+IN_1") (pintype "input"))
    )
    (net (code "47") (name "Net-(U20C-K)") (class "Default")
      (node (ref "C70") (pin "1") (pinfunction "1_1") (pintype "passive"))
      (node (ref "R78") (pin "2") (pinfunction "2_2") (pintype "passive"))
      (node (ref "U20") (pin "6") (pinfunction "K_6") (pintype "passive"))
      (node (ref "U21") (pin "3") (pinfunction "-IN_3") (pintype "input"))
    )
    (net (code "48") (name "Net-(U22--IN)") (class "Default")
      (node (ref "C72") (pin "1") (pinfunction "1_1") (pintype "passive"))
      (node (ref "R82") (pin "1") (pinfunction "1_1") (pintype "passive"))
      (node (ref "U22") (pin "3") (pinfunction "-IN_3") (pintype "input"))
    )
    (net (code "49") (name "Net-(U23A-K)") (class "Default")
      (node (ref "R85") (pin "1") (pinfunction "1_1") (pintype "passive"))
      (node (ref "U23") (pin "1") (pinfunction "K_1") (pintype "passive"))
    )
    (net (code "50") (name "Net-(U23B-A)") (class "Default")
      (node (ref "R88") (pin "1") (pinfunction "1_1") (pintype "passive"))
      (node (ref "U23") (pin "4") (pinfunction "A_4") (pintype "passive"))
      (node (ref "U25") (pin "1") (pinfunction "+IN_1") (pintype "input"))
    )
    (net (code "51") (name "Net-(U23C-K)") (class "Default")
      (node (ref "C75") (pin "1") (pinfunction "1_1") (pintype "passive"))
      (node (ref "R84") (pin "2") (pinfunction "2_2") (pintype "passive"))
      (node (ref "U23") (pin "6") (pinfunction "K_6") (pintype "passive"))
      (node (ref "U24") (pin "3") (pinfunction "-IN_3") (pintype "input"))
    )
    (net (code "52") (name "Net-(U25--IN)") (class "Default")
      (node (ref "C77") (pin "1") (pinfunction "1_1") (pintype "passive"))
      (node (ref "R87") (pin "1") (pinfunction "1_1") (pintype "passive"))
      (node (ref "U25") (pin "3") (pinfunction "-IN_3") (pintype "input"))
    )
    (net (code "53") (name "unconnected-(P7-Pad1)") (class "Default")
      (node (ref "P7") (pin "1") (pinfunction "1_1") (pintype "passive"))
    )
    (net (code "54") (name "unconnected-(P7-Pad2)") (class "Default")
      (node (ref "P7") (pin "2") (pinfunction "2_2") (pintype "passive"))
    )
    (net (code "55") (name "unconnected-(P8-Pad1)") (class "Default")
      (node (ref "P8") (pin "1") (pinfunction "1_1") (pintype "passive"))
    )
    (net (code "56") (name "unconnected-(P8-Pad2)") (class "Default")
      (node (ref "P8") (pin "2") (pinfunction "2_2") (pintype "passive"))
    )
    (net (code "57") (name "unconnected-(P9-Pad1)") (class "Default")
      (node (ref "P9") (pin "1") (pinfunction "1_1") (pintype "passive"))
    )
    (net (code "58") (name "unconnected-(P9-Pad2)") (class "Default")
      (node (ref "P9") (pin "2") (pinfunction "2_2") (pintype "passive"))
    )
    (net (code "59") (name "unconnected-(P10-Pad1)") (class "Default")
      (node (ref "P10") (pin "1") (pinfunction "1_1") (pintype "passive"))
    )
    (net (code "60") (name "unconnected-(P10-Pad2)") (class "Default")
      (node (ref "P10") (pin "2") (pinfunction "2_2") (pintype "passive"))
    )
  )
)
